# Filter5.net
KiCad netlist of a schematic drawn in Altium Designer
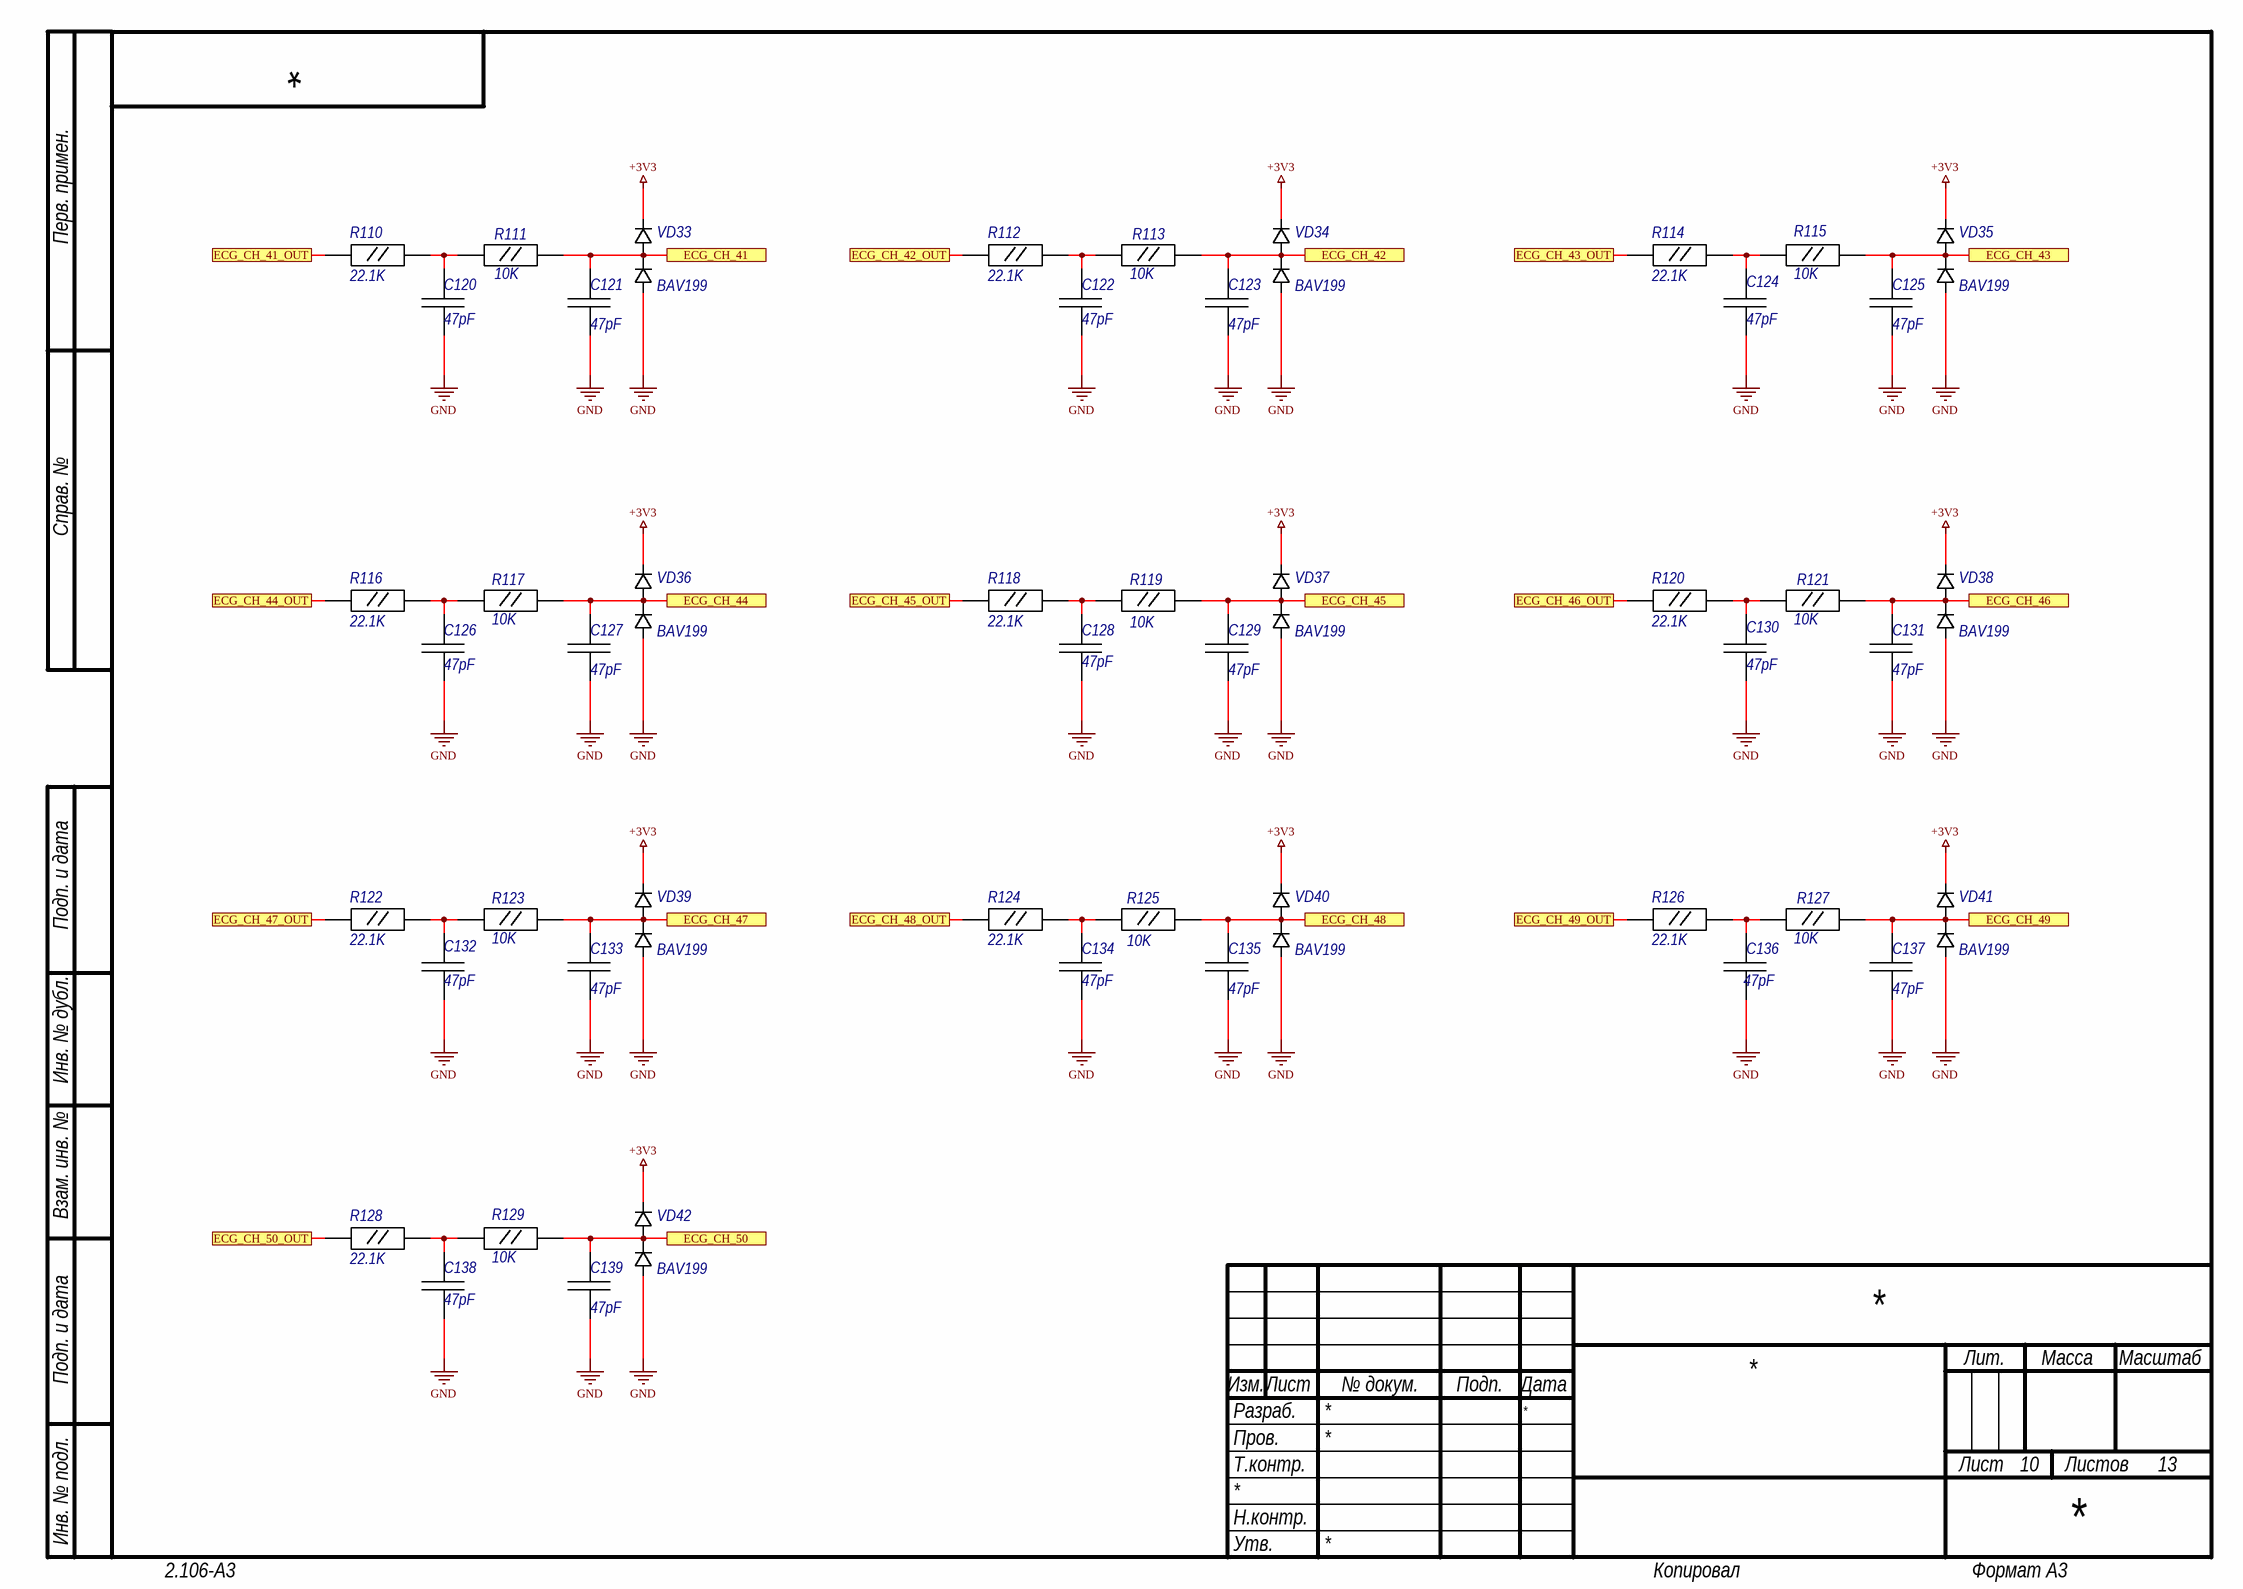
[diagram p0: Filter5.SchDoc]

(export (version "E")
  (design (tool "Eeschema 10.0.6"))
  (components
    (comp (ref "C120")
      (value "47pF")
      (footprint "C0603")
      (description "Ceramic Capacitor SMD")
      (libsource (lib "GOST") (part "CC_SMD_0603"))
    )
    (comp (ref "C121")
      (value "47pF")
      (footprint "C0603")
      (description "Ceramic Capacitor SMD")
      (libsource (lib "GOST") (part "CC_SMD_0603"))
    )
    (comp (ref "C122")
      (value "47pF")
      (footprint "C0603")
      (description "Ceramic Capacitor SMD")
      (libsource (lib "GOST") (part "CC_SMD_0603"))
    )
    (comp (ref "C123")
      (value "47pF")
      (footprint "C0603")
      (description "Ceramic Capacitor SMD")
      (libsource (lib "GOST") (part "CC_SMD_0603"))
    )
    (comp (ref "C124")
      (value "47pF")
      (footprint "C0603")
      (description "Ceramic Capacitor SMD")
      (libsource (lib "GOST") (part "CC_SMD_0603"))
    )
    (comp (ref "C125")
      (value "47pF")
      (footprint "C0603")
      (description "Ceramic Capacitor SMD")
      (libsource (lib "GOST") (part "CC_SMD_0603"))
    )
    (comp (ref "C126")
      (value "47pF")
      (footprint "C0603")
      (description "Ceramic Capacitor SMD")
      (libsource (lib "GOST") (part "CC_SMD_0603"))
    )
    (comp (ref "C127")
      (value "47pF")
      (footprint "C0603")
      (description "Ceramic Capacitor SMD")
      (libsource (lib "GOST") (part "CC_SMD_0603"))
    )
    (comp (ref "C128")
      (value "47pF")
      (footprint "C0603")
      (description "Ceramic Capacitor SMD")
      (libsource (lib "GOST") (part "CC_SMD_0603"))
    )
    (comp (ref "C129")
      (value "47pF")
      (footprint "C0603")
      (description "Ceramic Capacitor SMD")
      (libsource (lib "GOST") (part "CC_SMD_0603"))
    )
    (comp (ref "C130")
      (value "47pF")
      (footprint "C0603")
      (description "Ceramic Capacitor SMD")
      (libsource (lib "GOST") (part "CC_SMD_0603"))
    )
    (comp (ref "C131")
      (value "47pF")
      (footprint "C0603")
      (description "Ceramic Capacitor SMD")
      (libsource (lib "GOST") (part "CC_SMD_0603"))
    )
    (comp (ref "C132")
      (value "47pF")
      (footprint "C0603")
      (description "Ceramic Capacitor SMD")
      (libsource (lib "GOST") (part "CC_SMD_0603"))
    )
    (comp (ref "C133")
      (value "47pF")
      (footprint "C0603")
      (description "Ceramic Capacitor SMD")
      (libsource (lib "GOST") (part "CC_SMD_0603"))
    )
    (comp (ref "C134")
      (value "47pF")
      (footprint "C0603")
      (description "Ceramic Capacitor SMD")
      (libsource (lib "GOST") (part "CC_SMD_0603"))
    )
    (comp (ref "C135")
      (value "47pF")
      (footprint "C0603")
      (description "Ceramic Capacitor SMD")
      (libsource (lib "GOST") (part "CC_SMD_0603"))
    )
    (comp (ref "C136")
      (value "47pF")
      (footprint "C0603")
      (description "Ceramic Capacitor SMD")
      (libsource (lib "GOST") (part "CC_SMD_0603"))
    )
    (comp (ref "C137")
      (value "47pF")
      (footprint "C0603")
      (description "Ceramic Capacitor SMD")
      (libsource (lib "GOST") (part "CC_SMD_0603"))
    )
    (comp (ref "C138")
      (value "47pF")
      (footprint "C0603")
      (description "Ceramic Capacitor SMD")
      (libsource (lib "GOST") (part "CC_SMD_0603"))
    )
    (comp (ref "C139")
      (value "47pF")
      (footprint "C0603")
      (description "Ceramic Capacitor SMD")
      (libsource (lib "GOST") (part "CC_SMD_0603"))
    )
    (comp (ref "R110")
      (value "22.1K")
      (footprint "R0603")
      (description "Resistor SMD")
      (libsource (lib "GOST") (part "R0603"))
    )
    (comp (ref "R111")
      (value "10K")
      (footprint "R0603")
      (description "Resistor SMD")
      (libsource (lib "GOST") (part "R0603"))
    )
    (comp (ref "R112")
      (value "22.1K")
      (footprint "R0603")
      (description "Resistor SMD")
      (libsource (lib "GOST") (part "R0603"))
    )
    (comp (ref "R113")
      (value "10K")
      (footprint "R0603")
      (description "Resistor SMD")
      (libsource (lib "GOST") (part "R0603"))
    )
    (comp (ref "R114")
      (value "22.1K")
      (footprint "R0603")
      (description "Resistor SMD")
      (libsource (lib "GOST") (part "R0603"))
    )
    (comp (ref "R115")
      (value "10K")
      (footprint "R0603")
      (description "Resistor SMD")
      (libsource (lib "GOST") (part "R0603"))
    )
    (comp (ref "R116")
      (value "22.1K")
      (footprint "R0603")
      (description "Resistor SMD")
      (libsource (lib "GOST") (part "R0603"))
    )
    (comp (ref "R117")
      (value "10K")
      (footprint "R0603")
      (description "Resistor SMD")
      (libsource (lib "GOST") (part "R0603"))
    )
    (comp (ref "R118")
      (value "22.1K")
      (footprint "R0603")
      (description "Resistor SMD")
      (libsource (lib "GOST") (part "R0603"))
    )
    (comp (ref "R119")
      (value "10K")
      (footprint "R0603")
      (description "Resistor SMD")
      (libsource (lib "GOST") (part "R0603"))
    )
    (comp (ref "R120")
      (value "22.1K")
      (footprint "R0603")
      (description "Resistor SMD")
      (libsource (lib "GOST") (part "R0603"))
    )
    (comp (ref "R121")
      (value "10K")
      (footprint "R0603")
      (description "Resistor SMD")
      (libsource (lib "GOST") (part "R0603"))
    )
    (comp (ref "R122")
      (value "22.1K")
      (footprint "R0603")
      (description "Resistor SMD")
      (libsource (lib "GOST") (part "R0603"))
    )
    (comp (ref "R123")
      (value "10K")
      (footprint "R0603")
      (description "Resistor SMD")
      (libsource (lib "GOST") (part "R0603"))
    )
    (comp (ref "R124")
      (value "22.1K")
      (footprint "R0603")
      (description "Resistor SMD")
      (libsource (lib "GOST") (part "R0603"))
    )
    (comp (ref "R125")
      (value "10K")
      (footprint "R0603")
      (description "Resistor SMD")
      (libsource (lib "GOST") (part "R0603"))
    )
    (comp (ref "R126")
      (value "22.1K")
      (footprint "R0603")
      (description "Resistor SMD")
      (libsource (lib "GOST") (part "R0603"))
    )
    (comp (ref "R127")
      (value "10K")
      (footprint "R0603")
      (description "Resistor SMD")
      (libsource (lib "GOST") (part "R0603"))
    )
    (comp (ref "R128")
      (value "22.1K")
      (footprint "R0603")
      (description "Resistor SMD")
      (libsource (lib "GOST") (part "R0603"))
    )
    (comp (ref "R129")
      (value "10K")
      (footprint "R0603")
      (description "Resistor SMD")
      (libsource (lib "GOST") (part "R0603"))
    )
    (comp (ref "VD33")
      (value "BAV199")
      (footprint "SOT23")
      (description "Diod Schottky")
      (fields (field (name "MANUFACTURER PART NUMBER 1") "BAV199"))
      (libsource (lib "GOST") (part "DIODE_BAV199"))
    )
    (comp (ref "VD34")
      (value "BAV199")
      (footprint "SOT23")
      (description "Diod Schottky")
      (fields (field (name "MANUFACTURER PART NUMBER 1") "BAV199"))
      (libsource (lib "GOST") (part "DIODE_BAV199"))
    )
    (comp (ref "VD35")
      (value "BAV199")
      (footprint "SOT23")
      (description "Diod Schottky")
      (fields (field (name "MANUFACTURER PART NUMBER 1") "BAV199"))
      (libsource (lib "GOST") (part "DIODE_BAV199"))
    )
    (comp (ref "VD36")
      (value "BAV199")
      (footprint "SOT23")
      (description "Diod Schottky")
      (fields (field (name "MANUFACTURER PART NUMBER 1") "BAV199"))
      (libsource (lib "GOST") (part "DIODE_BAV199"))
    )
    (comp (ref "VD37")
      (value "BAV199")
      (footprint "SOT23")
      (description "Diod Schottky")
      (fields (field (name "MANUFACTURER PART NUMBER 1") "BAV199"))
      (libsource (lib "GOST") (part "DIODE_BAV199"))
    )
    (comp (ref "VD38")
      (value "BAV199")
      (footprint "SOT23")
      (description "Diod Schottky")
      (fields (field (name "MANUFACTURER PART NUMBER 1") "BAV199"))
      (libsource (lib "GOST") (part "DIODE_BAV199"))
    )
    (comp (ref "VD39")
      (value "BAV199")
      (footprint "SOT23")
      (description "Diod Schottky")
      (fields (field (name "MANUFACTURER PART NUMBER 1") "BAV199"))
      (libsource (lib "GOST") (part "DIODE_BAV199"))
    )
    (comp (ref "VD40")
      (value "BAV199")
      (footprint "SOT23")
      (description "Diod Schottky")
      (fields (field (name "MANUFACTURER PART NUMBER 1") "BAV199"))
      (libsource (lib "GOST") (part "DIODE_BAV199"))
    )
    (comp (ref "VD41")
      (value "BAV199")
      (footprint "SOT23")
      (description "Diod Schottky")
      (fields (field (name "MANUFACTURER PART NUMBER 1") "BAV199"))
      (libsource (lib "GOST") (part "DIODE_BAV199"))
    )
    (comp (ref "VD42")
      (value "BAV199")
      (footprint "SOT23")
      (description "Diod Schottky")
      (fields (field (name "MANUFACTURER PART NUMBER 1") "BAV199"))
      (libsource (lib "GOST") (part "DIODE_BAV199"))
    )
  )
  (nets
    (net (code "1") (name "+3V3") (class "Default")
      (node (ref "VD33") (pin "2") (pinfunction "2_2") (pintype "passive"))
      (node (ref "VD34") (pin "2") (pinfunction "2_2") (pintype "passive"))
      (node (ref "VD35") (pin "2") (pinfunction "2_2") (pintype "passive"))
      (node (ref "VD36") (pin "2") (pinfunction "2_2") (pintype "passive"))
      (node (ref "VD37") (pin "2") (pinfunction "2_2") (pintype "passive"))
      (node (ref "VD38") (pin "2") (pinfunction "2_2") (pintype "passive"))
      (node (ref "VD39") (pin "2") (pinfunction "2_2") (pintype "passive"))
      (node (ref "VD40") (pin "2") (pinfunction "2_2") (pintype "passive"))
      (node (ref "VD41") (pin "2") (pinfunction "2_2") (pintype "passive"))
      (node (ref "VD42") (pin "2") (pinfunction "2_2") (pintype "passive"))
    )
    (net (code "2") (name "/ECG_CH_41") (class "Default")
      (node (ref "C121") (pin "2") (pinfunction "2_2") (pintype "passive"))
      (node (ref "R111") (pin "2") (pinfunction "2_2") (pintype "passive"))
      (node (ref "VD33") (pin "3") (pinfunction "3_3") (pintype "passive"))
    )
    (net (code "3") (name "/ECG_CH_41_OUT") (class "Default")
      (node (ref "R110") (pin "1") (pinfunction "1_1") (pintype "passive"))
    )
    (net (code "4") (name "/ECG_CH_42") (class "Default")
      (node (ref "C123") (pin "2") (pinfunction "2_2") (pintype "passive"))
      (node (ref "R113") (pin "2") (pinfunction "2_2") (pintype "passive"))
      (node (ref "VD34") (pin "3") (pinfunction "3_3") (pintype "passive"))
    )
    (net (code "5") (name "/ECG_CH_42_OUT") (class "Default")
      (node (ref "R112") (pin "1") (pinfunction "1_1") (pintype "passive"))
    )
    (net (code "6") (name "/ECG_CH_43") (class "Default")
      (node (ref "C125") (pin "2") (pinfunction "2_2") (pintype "passive"))
      (node (ref "R115") (pin "2") (pinfunction "2_2") (pintype "passive"))
      (node (ref "VD35") (pin "3") (pinfunction "3_3") (pintype "passive"))
    )
    (net (code "7") (name "/ECG_CH_43_OUT") (class "Default")
      (node (ref "R114") (pin "1") (pinfunction "1_1") (pintype "passive"))
    )
    (net (code "8") (name "/ECG_CH_44") (class "Default")
      (node (ref "C127") (pin "2") (pinfunction "2_2") (pintype "passive"))
      (node (ref "R117") (pin "2") (pinfunction "2_2") (pintype "passive"))
      (node (ref "VD36") (pin "3") (pinfunction "3_3") (pintype "passive"))
    )
    (net (code "9") (name "/ECG_CH_44_OUT") (class "Default")
      (node (ref "R116") (pin "1") (pinfunction "1_1") (pintype "passive"))
    )
    (net (code "10") (name "/ECG_CH_45") (class "Default")
      (node (ref "C129") (pin "2") (pinfunction "2_2") (pintype "passive"))
      (node (ref "R119") (pin "2") (pinfunction "2_2") (pintype "passive"))
      (node (ref "VD37") (pin "3") (pinfunction "3_3") (pintype "passive"))
    )
    (net (code "11") (name "/ECG_CH_45_OUT") (class "Default")
      (node (ref "R118") (pin "1") (pinfunction "1_1") (pintype "passive"))
    )
    (net (code "12") (name "/ECG_CH_46") (class "Default")
      (node (ref "C131") (pin "2") (pinfunction "2_2") (pintype "passive"))
      (node (ref "R121") (pin "2") (pinfunction "2_2") (pintype "passive"))
      (node (ref "VD38") (pin "3") (pinfunction "3_3") (pintype "passive"))
    )
    (net (code "13") (name "/ECG_CH_46_OUT") (class "Default")
      (node (ref "R120") (pin "1") (pinfunction "1_1") (pintype "passive"))
    )
    (net (code "14") (name "/ECG_CH_47") (class "Default")
      (node (ref "C133") (pin "2") (pinfunction "2_2") (pintype "passive"))
      (node (ref "R123") (pin "2") (pinfunction "2_2") (pintype "passive"))
      (node (ref "VD39") (pin "3") (pinfunction "3_3") (pintype "passive"))
    )
    (net (code "15") (name "/ECG_CH_47_OUT") (class "Default")
      (node (ref "R122") (pin "1") (pinfunction "1_1") (pintype "passive"))
    )
    (net (code "16") (name "/ECG_CH_48") (class "Default")
      (node (ref "C135") (pin "2") (pinfunction "2_2") (pintype "passive"))
      (node (ref "R125") (pin "2") (pinfunction "2_2") (pintype "passive"))
      (node (ref "VD40") (pin "3") (pinfunction "3_3") (pintype "passive"))
    )
    (net (code "17") (name "/ECG_CH_48_OUT") (class "Default")
      (node (ref "R124") (pin "1") (pinfunction "1_1") (pintype "passive"))
    )
    (net (code "18") (name "/ECG_CH_49") (class "Default")
      (node (ref "C137") (pin "2") (pinfunction "2_2") (pintype "passive"))
      (node (ref "R127") (pin "2") (pinfunction "2_2") (pintype "passive"))
      (node (ref "VD41") (pin "3") (pinfunction "3_3") (pintype "passive"))
    )
    (net (code "19") (name "/ECG_CH_49_OUT") (class "Default")
      (node (ref "R126") (pin "1") (pinfunction "1_1") (pintype "passive"))
    )
    (net (code "20") (name "/ECG_CH_50") (class "Default")
      (node (ref "C139") (pin "2") (pinfunction "2_2") (pintype "passive"))
      (node (ref "R129") (pin "2") (pinfunction "2_2") (pintype "passive"))
      (node (ref "VD42") (pin "3") (pinfunction "3_3") (pintype "passive"))
    )
    (net (code "21") (name "/ECG_CH_50_OUT") (class "Default")
      (node (ref "R128") (pin "1") (pinfunction "1_1") (pintype "passive"))
    )
    (net (code "22") (name "GND") (class "Default")
      (node (ref "C120") (pin "1") (pinfunction "1_1") (pintype "passive"))
      (node (ref "C121") (pin "1") (pinfunction "1_1") (pintype "passive"))
      (node (ref "C122") (pin "1") (pinfunction "1_1") (pintype "passive"))
      (node (ref "C123") (pin "1") (pinfunction "1_1") (pintype "passive"))
      (node (ref "C124") (pin "1") (pinfunction "1_1") (pintype "passive"))
      (node (ref "C125") (pin "1") (pinfunction "1_1") (pintype "passive"))
      (node (ref "C126") (pin "1") (pinfunction "1_1") (pintype "passive"))
      (node (ref "C127") (pin "1") (pinfunction "1_1") (pintype "passive"))
      (node (ref "C128") (pin "1") (pinfunction "1_1") (pintype "passive"))
      (node (ref "C129") (pin "1") (pinfunction "1_1") (pintype "passive"))
      (node (ref "C130") (pin "1") (pinfunction "1_1") (pintype "passive"))
      (node (ref "C131") (pin "1") (pinfunction "1_1") (pintype "passive"))
      (node (ref "C132") (pin "1") (pinfunction "1_1") (pintype "passive"))
      (node (ref "C133") (pin "1") (pinfunction "1_1") (pintype "passive"))
      (node (ref "C134") (pin "1") (pinfunction "1_1") (pintype "passive"))
      (node (ref "C135") (pin "1") (pinfunction "1_1") (pintype "passive"))
      (node (ref "C136") (pin "1") (pinfunction "1_1") (pintype "passive"))
      (node (ref "C137") (pin "1") (pinfunction "1_1") (pintype "passive"))
      (node (ref "C138") (pin "1") (pinfunction "1_1") (pintype "passive"))
      (node (ref "C139") (pin "1") (pinfunction "1_1") (pintype "passive"))
      (node (ref "VD33") (pin "1") (pinfunction "1_1") (pintype "passive"))
      (node (ref "VD34") (pin "1") (pinfunction "1_1") (pintype "passive"))
      (node (ref "VD35") (pin "1") (pinfunction "1_1") (pintype "passive"))
      (node (ref "VD36") (pin "1") (pinfunction "1_1") (pintype "passive"))
      (node (ref "VD37") (pin "1") (pinfunction "1_1") (pintype "passive"))
      (node (ref "VD38") (pin "1") (pinfunction "1_1") (pintype "passive"))
      (node (ref "VD39") (pin "1") (pinfunction "1_1") (pintype "passive"))
      (node (ref "VD40") (pin "1") (pinfunction "1_1") (pintype "passive"))
      (node (ref "VD41") (pin "1") (pinfunction "1_1") (pintype "passive"))
      (node (ref "VD42") (pin "1") (pinfunction "1_1") (pintype "passive"))
    )
    (net (code "23") (name "Net-(C120-Pad2)") (class "Default")
      (node (ref "C120") (pin "2") (pinfunction "2_2") (pintype "passive"))
      (node (ref "R110") (pin "2") (pinfunction "2_2") (pintype "passive"))
      (node (ref "R111") (pin "1") (pinfunction "1_1") (pintype "passive"))
    )
    (net (code "24") (name "Net-(C122-Pad2)") (class "Default")
      (node (ref "C122") (pin "2") (pinfunction "2_2") (pintype "passive"))
      (node (ref "R112") (pin "2") (pinfunction "2_2") (pintype "passive"))
      (node (ref "R113") (pin "1") (pinfunction "1_1") (pintype "passive"))
    )
    (net (code "25") (name "Net-(C124-Pad2)") (class "Default")
      (node (ref "C124") (pin "2") (pinfunction "2_2") (pintype "passive"))
      (node (ref "R114") (pin "2") (pinfunction "2_2") (pintype "passive"))
      (node (ref "R115") (pin "1") (pinfunction "1_1") (pintype "passive"))
    )
    (net (code "26") (name "Net-(C126-Pad2)") (class "Default")
      (node (ref "C126") (pin "2") (pinfunction "2_2") (pintype "passive"))
      (node (ref "R116") (pin "2") (pinfunction "2_2") (pintype "passive"))
      (node (ref "R117") (pin "1") (pinfunction "1_1") (pintype "passive"))
    )
    (net (code "27") (name "Net-(C128-Pad2)") (class "Default")
      (node (ref "C128") (pin "2") (pinfunction "2_2") (pintype "passive"))
      (node (ref "R118") (pin "2") (pinfunction "2_2") (pintype "passive"))
      (node (ref "R119") (pin "1") (pinfunction "1_1") (pintype "passive"))
    )
    (net (code "28") (name "Net-(C130-Pad2)") (class "Default")
      (node (ref "C130") (pin "2") (pinfunction "2_2") (pintype "passive"))
      (node (ref "R120") (pin "2") (pinfunction "2_2") (pintype "passive"))
      (node (ref "R121") (pin "1") (pinfunction "1_1") (pintype "passive"))
    )
    (net (code "29") (name "Net-(C132-Pad2)") (class "Default")
      (node (ref "C132") (pin "2") (pinfunction "2_2") (pintype "passive"))
      (node (ref "R122") (pin "2") (pinfunction "2_2") (pintype "passive"))
      (node (ref "R123") (pin "1") (pinfunction "1_1") (pintype "passive"))
    )
    (net (code "30") (name "Net-(C134-Pad2)") (class "Default")
      (node (ref "C134") (pin "2") (pinfunction "2_2") (pintype "passive"))
      (node (ref "R124") (pin "2") (pinfunction "2_2") (pintype "passive"))
      (node (ref "R125") (pin "1") (pinfunction "1_1") (pintype "passive"))
    )
    (net (code "31") (name "Net-(C136-Pad2)") (class "Default")
      (node (ref "C136") (pin "2") (pinfunction "2_2") (pintype "passive"))
      (node (ref "R126") (pin "2") (pinfunction "2_2") (pintype "passive"))
      (node (ref "R127") (pin "1") (pinfunction "1_1") (pintype "passive"))
    )
    (net (code "32") (name "Net-(C138-Pad2)") (class "Default")
      (node (ref "C138") (pin "2") (pinfunction "2_2") (pintype "passive"))
      (node (ref "R128") (pin "2") (pinfunction "2_2") (pintype "passive"))
      (node (ref "R129") (pin "1") (pinfunction "1_1") (pintype "passive"))
    )
  )
)
